# cradle_venus.net
KiCad netlist of a schematic drawn in EAGLE
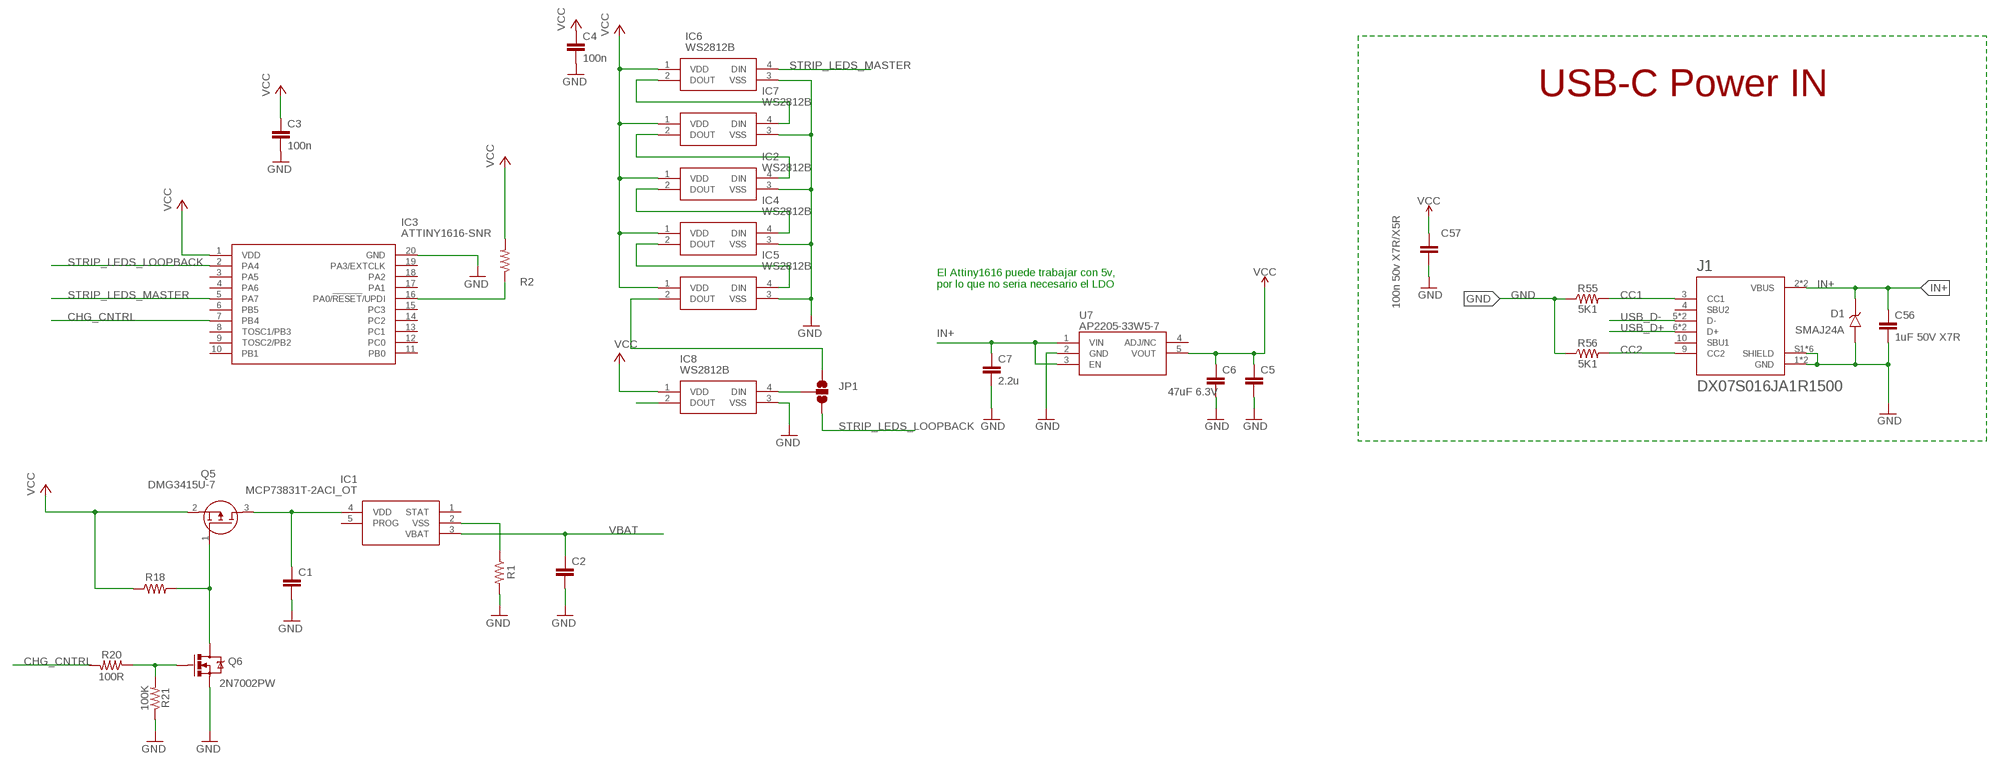
[diagram p0: schematic, sheet 1]

(export (version "E")
  (design (tool "Eeschema 10.0.6"))
  (components
    (comp (ref "C1")
      (value "C-EUC0805")
      (footprint "eagle-import:C0805")
      (libsource (lib "eagle-import") (part "C-EUC0805"))
    )
    (comp (ref "C2")
      (value "C-EUC0805")
      (footprint "eagle-import:C0805")
      (libsource (lib "eagle-import") (part "C-EUC0805"))
    )
    (comp (ref "C3")
      (value "100n")
      (footprint "eagle-import:C0805")
      (libsource (lib "eagle-import") (part "C-EUC0805"))
    )
    (comp (ref "C4")
      (value "100n")
      (footprint "eagle-import:C0805")
      (libsource (lib "eagle-import") (part "C-EUC0805"))
    )
    (comp (ref "C5")
      (value "C-EUC0805")
      (footprint "eagle-import:C0805")
      (libsource (lib "eagle-import") (part "C-EUC0805"))
    )
    (comp (ref "C6")
      (value "47uF 6.3V")
      (footprint "eagle-import:0603-CAP")
      (libsource (lib "eagle-import") (part "4.7UF-6.3V-10%(0603)0603"))
    )
    (comp (ref "C7")
      (value "2.2u")
      (footprint "eagle-import:0603-CAP")
      (libsource (lib "eagle-import") (part "4.7UF-6.3V-10%(0603)0603"))
    )
    (comp (ref "C56")
      (value "1uF 50V X7R")
      (footprint "eagle-import:0805")
      (libsource (lib "eagle-import") (part "CAP0805"))
    )
    (comp (ref "C57")
      (value "100n 50v X7R/X5R")
      (footprint "eagle-import:0805")
      (libsource (lib "eagle-import") (part "CAP0805"))
    )
    (comp (ref "D1")
      (value "SMAJ24A")
      (footprint "eagle-import:DIOM4325X244N")
      (fields (field (name "MF") "Micro Commercial Components") (field (name "MP") "3SMAJ5934B"))
      (libsource (lib "eagle-import") (part "3SMAJ5934B"))
    )
    (comp (ref "IC1")
      (value "MCP73831T-2ACI_OT")
      (footprint "eagle-import:SOT95P270X145-5N")
      (fields
        (field (name "ARROW_PART_NUMBER") "MCP73831T-2ACI/OT")
        (field (name "MOUSER_PART_NUMBER") "579-MCP73831T-2ACIOT")
      )
      (libsource (lib "eagle-import") (part "MCP73831T-2ACI_OT"))
    )
    (comp (ref "IC2")
      (value "WS2812B")
      (footprint "eagle-import:WS2812B")
      (libsource (lib "eagle-import") (part "WS2812B"))
    )
    (comp (ref "IC3")
      (value "ATTINY1616-SNR")
      (footprint "eagle-import:SOIC127P1030X265-20N")
      (fields (field (name "MOUSER_PART_NUMBER") "556-ATTINY1616SNR"))
      (libsource (lib "eagle-import") (part "ATTINY1616-SNR"))
    )
    (comp (ref "IC4")
      (value "WS2812B")
      (footprint "eagle-import:WS2812B")
      (libsource (lib "eagle-import") (part "WS2812B"))
    )
    (comp (ref "IC5")
      (value "WS2812B")
      (footprint "eagle-import:WS2812B")
      (libsource (lib "eagle-import") (part "WS2812B"))
    )
    (comp (ref "IC6")
      (value "WS2812B")
      (footprint "eagle-import:WS2812B")
      (libsource (lib "eagle-import") (part "WS2812B"))
    )
    (comp (ref "IC7")
      (value "WS2812B")
      (footprint "eagle-import:WS2812B")
      (libsource (lib "eagle-import") (part "WS2812B"))
    )
    (comp (ref "IC8")
      (value "WS2812B")
      (footprint "eagle-import:WS2812B")
      (libsource (lib "eagle-import") (part "WS2812B"))
    )
    (comp (ref "J1")
      (value "DX07S016JA1R1500")
      (footprint "eagle-import:JAE_DX07S016JA1R1500")
      (fields
        (field (name "DIGI-KEY_PART_NUMBER") "670-DX07S016JA1R1500CT-ND")
        (field (name "MF") "JAE Electronics")
      )
      (libsource (lib "eagle-import") (part "DX07S016JA1R1500"))
    )
    (comp (ref "JP1")
      (value "JUMPER-SMT_3_NO_SILK")
      (footprint "eagle-import:SMT-JUMPER_3_NO_SILK")
      (libsource (lib "eagle-import") (part "JUMPER-SMT_3_NO_SILK"))
    )
    (comp (ref "Q5")
      (value "DMG3415U-7")
      (footprint "eagle-import:SSM3J332RLFT")
      (fields
        (field (name "ARROW_PART_NUMBER") "SSM3J338R,LF")
        (field (name "MOUSER_PART_NUMBER") "757-SSM3J338RLF")
      )
      (libsource (lib "eagle-import") (part "SSM3J338R,LF"))
    )
    (comp (ref "Q6")
      (value "2N7002PW")
      (footprint "eagle-import:SOT323")
      (libsource (lib "eagle-import") (part "MOSFET-NCHANNEL2N7002PW"))
    )
    (comp (ref "R1")
      (value "RESISTOR0805")
      (footprint "eagle-import:0805")
      (libsource (lib "eagle-import") (part "RESISTOR0805"))
    )
    (comp (ref "R2")
      (value "RESISTOR0805")
      (footprint "eagle-import:0805")
      (libsource (lib "eagle-import") (part "RESISTOR0805"))
    )
    (comp (ref "R18")
      (value "RESISTOR0805")
      (footprint "eagle-import:0805")
      (libsource (lib "eagle-import") (part "RESISTOR0805"))
    )
    (comp (ref "R20")
      (value "100R")
      (footprint "eagle-import:0805")
      (libsource (lib "eagle-import") (part "RESISTOR0805"))
    )
    (comp (ref "R21")
      (value "100K")
      (footprint "eagle-import:0805")
      (libsource (lib "eagle-import") (part "RESISTOR0805"))
    )
    (comp (ref "R55")
      (value "5K1")
      (footprint "eagle-import:0805")
      (libsource (lib "eagle-import") (part "RESISTOR0805"))
    )
    (comp (ref "R56")
      (value "5K1")
      (footprint "eagle-import:0805")
      (libsource (lib "eagle-import") (part "RESISTOR0805"))
    )
    (comp (ref "U7")
      (value "AP2205-33W5-7")
      (footprint "eagle-import:SOT95P282X145-5N")
      (fields
        (field (name "MANUFACTURER_PART_NUMBER") "AP2205-W5-7")
        (field (name "MOUSER_PART_NUMBER") "621-AP2205-W5-7")
      )
      (libsource (lib "eagle-import") (part "AP2205-W5-7"))
    )
  )
  (nets
    (net (code "1") (name "/CC1") (class "Default")
      (node (ref "J1") (pin "3") (pinfunction "CC1_3") (pintype "passive"))
      (node (ref "R55") (pin "2") (pinfunction "2_2") (pintype "passive"))
    )
    (net (code "2") (name "/CC2") (class "Default")
      (node (ref "J1") (pin "9") (pinfunction "CC2_9") (pintype "passive"))
      (node (ref "R56") (pin "2") (pinfunction "2_2") (pintype "passive"))
    )
    (net (code "3") (name "/CHG_CNTRL") (class "Default")
      (node (ref "IC3") (pin "7") (pinfunction "PB4_7") (pintype "bidirectional"))
      (node (ref "R20") (pin "2") (pinfunction "2_2") (pintype "passive"))
    )
    (net (code "4") (name "/STRIP_LEDS_LOOPBACK") (class "Default")
      (node (ref "IC3") (pin "2") (pinfunction "PA4_2") (pintype "bidirectional"))
      (node (ref "JP1") (pin "3") (pinfunction "3_3") (pintype "passive"))
    )
    (net (code "5") (name "/STRIP_LEDS_MASTER") (class "Default")
      (node (ref "IC3") (pin "5") (pinfunction "PA7_5") (pintype "bidirectional"))
      (node (ref "IC6") (pin "4") (pinfunction "DIN_4") (pintype "bidirectional"))
    )
    (net (code "6") (name "/USB_D+") (class "Default")
      (node (ref "J1") (pin "6") (pinfunction "D+_6") (pintype "passive"))
      (node (ref "J1") (pin "7") (pinfunction "D+_7") (pintype "passive"))
    )
    (net (code "7") (name "/USB_D-") (class "Default")
      (node (ref "J1") (pin "5") (pinfunction "D-_5") (pintype "passive"))
      (node (ref "J1") (pin "8") (pinfunction "D-_8") (pintype "passive"))
    )
    (net (code "8") (name "/VBAT") (class "Default")
      (node (ref "C2") (pin "1") (pinfunction "1_1") (pintype "passive"))
      (node (ref "IC1") (pin "3") (pinfunction "VBAT_3") (pintype "bidirectional"))
    )
    (net (code "9") (name "GND") (class "Default")
      (node (ref "C1") (pin "2") (pinfunction "2_2") (pintype "passive"))
      (node (ref "C2") (pin "2") (pinfunction "2_2") (pintype "passive"))
      (node (ref "C3") (pin "2") (pinfunction "2_2") (pintype "passive"))
      (node (ref "C4") (pin "2") (pinfunction "2_2") (pintype "passive"))
      (node (ref "C5") (pin "2") (pinfunction "2_2") (pintype "passive"))
      (node (ref "C56") (pin "2") (pinfunction "2_2") (pintype "passive"))
      (node (ref "C57") (pin "2") (pinfunction "2_2") (pintype "passive"))
      (node (ref "C6") (pin "2") (pinfunction "2_2") (pintype "passive"))
      (node (ref "C7") (pin "2") (pinfunction "2_2") (pintype "passive"))
      (node (ref "D1") (pin "A") (pinfunction "A_A") (pintype "passive"))
      (node (ref "IC2") (pin "3") (pinfunction "VSS_3") (pintype "bidirectional"))
      (node (ref "IC3") (pin "20") (pinfunction "GND_20") (pintype "bidirectional"))
      (node (ref "IC4") (pin "3") (pinfunction "VSS_3") (pintype "bidirectional"))
      (node (ref "IC5") (pin "3") (pinfunction "VSS_3") (pintype "bidirectional"))
      (node (ref "IC6") (pin "3") (pinfunction "VSS_3") (pintype "bidirectional"))
      (node (ref "IC7") (pin "3") (pinfunction "VSS_3") (pintype "bidirectional"))
      (node (ref "IC8") (pin "3") (pinfunction "VSS_3") (pintype "bidirectional"))
      (node (ref "J1") (pin "1") (pinfunction "GND_1") (pintype "power_in"))
      (node (ref "J1") (pin "12") (pinfunction "GND_12") (pintype "power_in"))
      (node (ref "J1") (pin "S1") (pinfunction "SHIELD_S1") (pintype "passive"))
      (node (ref "J1") (pin "S2") (pinfunction "SHIELD_S2") (pintype "passive"))
      (node (ref "J1") (pin "S3") (pinfunction "SHIELD_S3") (pintype "passive"))
      (node (ref "J1") (pin "S4") (pinfunction "SHIELD_S4") (pintype "passive"))
      (node (ref "J1") (pin "S5") (pinfunction "SHIELD_S5") (pintype "passive"))
      (node (ref "J1") (pin "S6") (pinfunction "SHIELD_S6") (pintype "passive"))
      (node (ref "Q6") (pin "2") (pinfunction "S_2") (pintype "passive"))
      (node (ref "R1") (pin "2") (pinfunction "2_2") (pintype "passive"))
      (node (ref "R21") (pin "1") (pinfunction "1_1") (pintype "passive"))
      (node (ref "R55") (pin "1") (pinfunction "1_1") (pintype "passive"))
      (node (ref "R56") (pin "1") (pinfunction "1_1") (pintype "passive"))
      (node (ref "U7") (pin "2") (pinfunction "GND_2") (pintype "bidirectional"))
    )
    (net (code "10") (name "IN+") (class "Default")
      (node (ref "C56") (pin "1") (pinfunction "1_1") (pintype "passive"))
      (node (ref "C7") (pin "1") (pinfunction "1_1") (pintype "passive"))
      (node (ref "D1") (pin "C") (pinfunction "K_C") (pintype "passive"))
      (node (ref "J1") (pin "11") (pinfunction "VBUS_11") (pintype "power_in"))
      (node (ref "J1") (pin "2") (pinfunction "VBUS_2") (pintype "power_in"))
      (node (ref "U7") (pin "1") (pinfunction "VIN_1") (pintype "bidirectional"))
      (node (ref "U7") (pin "3") (pinfunction "EN_3") (pintype "bidirectional"))
    )
    (net (code "11") (name "Net-(IC1-VDD)") (class "Default")
      (node (ref "C1") (pin "1") (pinfunction "1_1") (pintype "passive"))
      (node (ref "IC1") (pin "4") (pinfunction "VDD_4") (pintype "bidirectional"))
      (node (ref "Q5") (pin "3") (pinfunction "D_3") (pintype "bidirectional"))
    )
    (net (code "12") (name "Net-(IC1-VSS)") (class "Default")
      (node (ref "IC1") (pin "2") (pinfunction "VSS_2") (pintype "bidirectional"))
      (node (ref "R1") (pin "1") (pinfunction "1_1") (pintype "passive"))
    )
    (net (code "13") (name "Net-(IC2-DIN)") (class "Default")
      (node (ref "IC2") (pin "4") (pinfunction "DIN_4") (pintype "bidirectional"))
      (node (ref "IC7") (pin "2") (pinfunction "DOUT_2") (pintype "bidirectional"))
    )
    (net (code "14") (name "Net-(IC2-DOUT)") (class "Default")
      (node (ref "IC2") (pin "2") (pinfunction "DOUT_2") (pintype "bidirectional"))
      (node (ref "IC4") (pin "4") (pinfunction "DIN_4") (pintype "bidirectional"))
    )
    (net (code "15") (name "Net-(IC3-PA0{slash}~{RESET}{slash}UPDI)") (class "Default")
      (node (ref "IC3") (pin "16") (pinfunction "PA0/~{RESET}/UPDI_16") (pintype "bidirectional"))
      (node (ref "R2") (pin "1") (pinfunction "1_1") (pintype "passive"))
    )
    (net (code "16") (name "Net-(IC4-DOUT)") (class "Default")
      (node (ref "IC4") (pin "2") (pinfunction "DOUT_2") (pintype "bidirectional"))
      (node (ref "IC5") (pin "4") (pinfunction "DIN_4") (pintype "bidirectional"))
    )
    (net (code "17") (name "Net-(IC5-DOUT)") (class "Default")
      (node (ref "IC5") (pin "2") (pinfunction "DOUT_2") (pintype "bidirectional"))
      (node (ref "JP1") (pin "1") (pinfunction "1_1") (pintype "passive"))
    )
    (net (code "18") (name "Net-(IC6-DOUT)") (class "Default")
      (node (ref "IC6") (pin "2") (pinfunction "DOUT_2") (pintype "bidirectional"))
      (node (ref "IC7") (pin "4") (pinfunction "DIN_4") (pintype "bidirectional"))
    )
    (net (code "19") (name "Net-(IC8-DIN)") (class "Default")
      (node (ref "IC8") (pin "4") (pinfunction "DIN_4") (pintype "bidirectional"))
      (node (ref "JP1") (pin "2") (pinfunction "2_2") (pintype "passive"))
    )
    (net (code "20") (name "Net-(Q5-G)") (class "Default")
      (node (ref "Q5") (pin "1") (pinfunction "G_1") (pintype "bidirectional"))
      (node (ref "Q6") (pin "3") (pinfunction "D_3") (pintype "passive"))
      (node (ref "R18") (pin "2") (pinfunction "2_2") (pintype "passive"))
    )
    (net (code "21") (name "Net-(Q6-G)") (class "Default")
      (node (ref "Q6") (pin "1") (pinfunction "G_1") (pintype "passive"))
      (node (ref "R20") (pin "1") (pinfunction "1_1") (pintype "passive"))
      (node (ref "R21") (pin "2") (pinfunction "2_2") (pintype "passive"))
    )
    (net (code "22") (name "VCC") (class "Default")
      (node (ref "C3") (pin "1") (pinfunction "1_1") (pintype "passive"))
      (node (ref "C4") (pin "1") (pinfunction "1_1") (pintype "passive"))
      (node (ref "C5") (pin "1") (pinfunction "1_1") (pintype "passive"))
      (node (ref "C57") (pin "1") (pinfunction "1_1") (pintype "passive"))
      (node (ref "C6") (pin "1") (pinfunction "1_1") (pintype "passive"))
      (node (ref "IC2") (pin "1") (pinfunction "VDD_1") (pintype "bidirectional"))
      (node (ref "IC3") (pin "1") (pinfunction "VDD_1") (pintype "bidirectional"))
      (node (ref "IC4") (pin "1") (pinfunction "VDD_1") (pintype "bidirectional"))
      (node (ref "IC5") (pin "1") (pinfunction "VDD_1") (pintype "bidirectional"))
      (node (ref "IC6") (pin "1") (pinfunction "VDD_1") (pintype "bidirectional"))
      (node (ref "IC7") (pin "1") (pinfunction "VDD_1") (pintype "bidirectional"))
      (node (ref "IC8") (pin "1") (pinfunction "VDD_1") (pintype "bidirectional"))
      (node (ref "Q5") (pin "2") (pinfunction "S_2") (pintype "bidirectional"))
      (node (ref "R18") (pin "1") (pinfunction "1_1") (pintype "passive"))
      (node (ref "R2") (pin "2") (pinfunction "2_2") (pintype "passive"))
      (node (ref "U7") (pin "5") (pinfunction "VOUT_5") (pintype "bidirectional"))
    )
    (net (code "23") (name "unconnected-(IC1-PROG-Pad5)") (class "Default")
      (node (ref "IC1") (pin "5") (pinfunction "PROG_5") (pintype "bidirectional"))
    )
    (net (code "24") (name "unconnected-(IC1-STAT-Pad1)") (class "Default")
      (node (ref "IC1") (pin "1") (pinfunction "STAT_1") (pintype "bidirectional"))
    )
    (net (code "25") (name "unconnected-(IC3-PA1-Pad17)") (class "Default")
      (node (ref "IC3") (pin "17") (pinfunction "PA1_17") (pintype "bidirectional"))
    )
    (net (code "26") (name "unconnected-(IC3-PA2-Pad18)") (class "Default")
      (node (ref "IC3") (pin "18") (pinfunction "PA2_18") (pintype "bidirectional"))
    )
    (net (code "27") (name "unconnected-(IC3-PA3{slash}EXTCLK-Pad19)") (class "Default")
      (node (ref "IC3") (pin "19") (pinfunction "PA3/EXTCLK_19") (pintype "bidirectional"))
    )
    (net (code "28") (name "unconnected-(IC3-PA5-Pad3)") (class "Default")
      (node (ref "IC3") (pin "3") (pinfunction "PA5_3") (pintype "bidirectional"))
    )
    (net (code "29") (name "unconnected-(IC3-PA6-Pad4)") (class "Default")
      (node (ref "IC3") (pin "4") (pinfunction "PA6_4") (pintype "bidirectional"))
    )
    (net (code "30") (name "unconnected-(IC3-PB0-Pad11)") (class "Default")
      (node (ref "IC3") (pin "11") (pinfunction "PB0_11") (pintype "bidirectional"))
    )
    (net (code "31") (name "unconnected-(IC3-PB1-Pad10)") (class "Default")
      (node (ref "IC3") (pin "10") (pinfunction "PB1_10") (pintype "bidirectional"))
    )
    (net (code "32") (name "unconnected-(IC3-PB5-Pad6)") (class "Default")
      (node (ref "IC3") (pin "6") (pinfunction "PB5_6") (pintype "bidirectional"))
    )
    (net (code "33") (name "unconnected-(IC3-PC0-Pad12)") (class "Default")
      (node (ref "IC3") (pin "12") (pinfunction "PC0_12") (pintype "bidirectional"))
    )
    (net (code "34") (name "unconnected-(IC3-PC1-Pad13)") (class "Default")
      (node (ref "IC3") (pin "13") (pinfunction "PC1_13") (pintype "bidirectional"))
    )
    (net (code "35") (name "unconnected-(IC3-PC2-Pad14)") (class "Default")
      (node (ref "IC3") (pin "14") (pinfunction "PC2_14") (pintype "bidirectional"))
    )
    (net (code "36") (name "unconnected-(IC3-PC3-Pad15)") (class "Default")
      (node (ref "IC3") (pin "15") (pinfunction "PC3_15") (pintype "bidirectional"))
    )
    (net (code "37") (name "unconnected-(IC3-TOSC1{slash}PB3-Pad8)") (class "Default")
      (node (ref "IC3") (pin "8") (pinfunction "TOSC1/PB3_8") (pintype "bidirectional"))
    )
    (net (code "38") (name "unconnected-(IC3-TOSC2{slash}PB2-Pad9)") (class "Default")
      (node (ref "IC3") (pin "9") (pinfunction "TOSC2/PB2_9") (pintype "bidirectional"))
    )
    (net (code "39") (name "unconnected-(IC8-DOUT-Pad2)") (class "Default")
      (node (ref "IC8") (pin "2") (pinfunction "DOUT_2") (pintype "bidirectional"))
    )
    (net (code "40") (name "unconnected-(J1-SBU1-Pad10)") (class "Default")
      (node (ref "J1") (pin "10") (pinfunction "SBU1_10") (pintype "passive"))
    )
    (net (code "41") (name "unconnected-(J1-SBU2-Pad4)") (class "Default")
      (node (ref "J1") (pin "4") (pinfunction "SBU2_4") (pintype "passive"))
    )
    (net (code "42") (name "unconnected-(U7-ADJ{slash}NC-Pad4)") (class "Default")
      (node (ref "U7") (pin "4") (pinfunction "ADJ/NC_4") (pintype "bidirectional"))
    )
  )
)
